# circuit.net
KiCad netlist of a schematic drawn in EAGLE
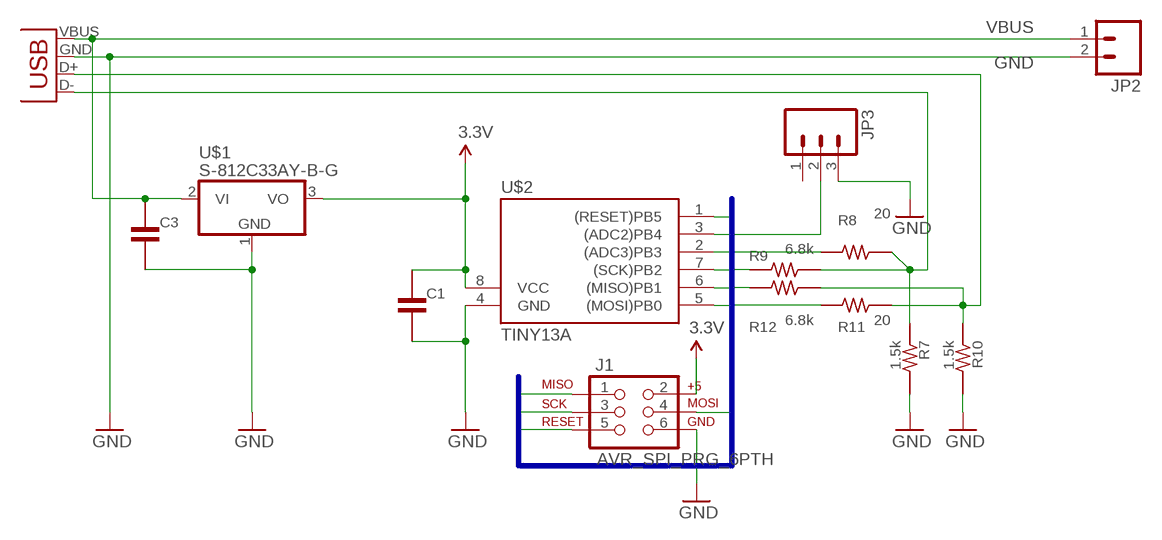
[diagram p0: schematic, sheet 1]

(export (version "E")
  (design (tool "Eeschema 10.0.6"))
  (components
    (comp (ref "C1")
      (value "C-50V-0302-2.54")
      (footprint "eagle-import:50-0302-2.54")
      (libsource (lib "eagle-import") (part "C-50V-0302-2.54"))
    )
    (comp (ref "C3")
      (value "C-50V-0302-2.54")
      (footprint "eagle-import:50-0302-2.54")
      (libsource (lib "eagle-import") (part "C-50V-0302-2.54"))
    )
    (comp (ref "J1")
      (value "AVR_SPI_PRG_6PTH")
      (footprint "eagle-import:2X3")
      (libsource (lib "eagle-import") (part "AVR_SPI_PRG_6PTH"))
    )
    (comp (ref "JP1")
      (value "USB-A-H")
      (footprint "eagle-import:USB-A-H")
      (libsource (lib "eagle-import") (part "USB-A-H"))
    )
    (comp (ref "JP2")
      (value "M02PTH")
      (footprint "eagle-import:1X02")
      (libsource (lib "eagle-import") (part "M02PTH"))
    )
    (comp (ref "JP3")
      (value "M03PTH")
      (footprint "eagle-import:1X03")
      (libsource (lib "eagle-import") (part "M03PTH"))
    )
    (comp (ref "R7")
      (value "1.5k")
      (footprint "eagle-import:1_4W-5.08V")
      (libsource (lib "eagle-import") (part "R-1/4W-05.08-V"))
    )
    (comp (ref "R8")
      (value "20")
      (footprint "eagle-import:1_4W-5.08V")
      (libsource (lib "eagle-import") (part "R-1/4W-05.08-V"))
    )
    (comp (ref "R9")
      (value "6.8k")
      (footprint "eagle-import:1_4W-5.08V")
      (libsource (lib "eagle-import") (part "R-1/4W-05.08-V"))
    )
    (comp (ref "R10")
      (value "1.5k")
      (footprint "eagle-import:1_4W-5.08V")
      (libsource (lib "eagle-import") (part "R-1/4W-05.08-V"))
    )
    (comp (ref "R11")
      (value "20")
      (footprint "eagle-import:1_4W-5.08V")
      (libsource (lib "eagle-import") (part "R-1/4W-05.08-V"))
    )
    (comp (ref "R12")
      (value "6.8k")
      (footprint "eagle-import:1_4W-5.08V")
      (libsource (lib "eagle-import") (part "R-1/4W-05.08-V"))
    )
    (comp (ref "U$1")
      (value "S-812C33AY-B-G")
      (footprint "eagle-import:TO-92")
      (libsource (lib "eagle-import") (part "S-812C"))
    )
    (comp (ref "U$2")
      (value "TINY13A")
      (footprint "eagle-import:DIL08")
      (libsource (lib "eagle-import") (part "TINY138P3"))
    )
  )
  (nets
    (net (code "1") (name "/MISO") (class "Default")
      (node (ref "J1") (pin "1") (pinfunction "1_1") (pintype "passive"))
      (node (ref "R12") (pin "PAD1") (pinfunction "1_PAD1") (pintype "passive"))
      (node (ref "U$2") (pin "6") (pinfunction "(MISO)PB1_6") (pintype "bidirectional"))
    )
    (net (code "2") (name "/MOSI") (class "Default")
      (node (ref "J1") (pin "4") (pinfunction "4_4") (pintype "passive"))
      (node (ref "R11") (pin "PAD1") (pinfunction "1_PAD1") (pintype "passive"))
      (node (ref "U$2") (pin "5") (pinfunction "(MOSI)PB0_5") (pintype "bidirectional"))
    )
    (net (code "3") (name "/RESET") (class "Default")
      (node (ref "J1") (pin "5") (pinfunction "5_5") (pintype "passive"))
      (node (ref "U$2") (pin "1") (pinfunction "(RESET)PB5_1") (pintype "bidirectional"))
    )
    (net (code "4") (name "/SCK") (class "Default")
      (node (ref "J1") (pin "3") (pinfunction "3_3") (pintype "passive"))
      (node (ref "R9") (pin "PAD1") (pinfunction "1_PAD1") (pintype "passive"))
      (node (ref "U$2") (pin "7") (pinfunction "(SCK)PB2_7") (pintype "bidirectional"))
    )
    (net (code "5") (name "/VBUS") (class "Default")
      (node (ref "C3") (pin "PAD1") (pinfunction "1_PAD1") (pintype "passive"))
      (node (ref "JP1") (pin "VBUS") (pinfunction "GND_VBUS") (pintype "bidirectional"))
      (node (ref "JP2") (pin "1") (pinfunction "1_1") (pintype "passive"))
      (node (ref "U$1") (pin "2") (pinfunction "VI_2") (pintype "input"))
    )
    (net (code "6") (name "3.3V") (class "Default")
      (node (ref "C1") (pin "PAD1") (pinfunction "1_PAD1") (pintype "passive"))
      (node (ref "J1") (pin "2") (pinfunction "2_2") (pintype "passive"))
      (node (ref "U$1") (pin "3") (pinfunction "VO_3") (pintype "passive"))
      (node (ref "U$2") (pin "8") (pinfunction "VCC_8") (pintype "power_in"))
    )
    (net (code "7") (name "GND") (class "Default")
      (node (ref "C1") (pin "PAD2") (pinfunction "2_PAD2") (pintype "passive"))
      (node (ref "C3") (pin "PAD2") (pinfunction "2_PAD2") (pintype "passive"))
      (node (ref "J1") (pin "6") (pinfunction "6_6") (pintype "passive"))
      (node (ref "JP1") (pin "GND") (pinfunction "VBUS_GND") (pintype "bidirectional"))
      (node (ref "JP2") (pin "2") (pinfunction "2_2") (pintype "passive"))
      (node (ref "JP3") (pin "3") (pinfunction "3_3") (pintype "passive"))
      (node (ref "R10") (pin "PAD2") (pinfunction "2_PAD2") (pintype "passive"))
      (node (ref "R7") (pin "PAD2") (pinfunction "2_PAD2") (pintype "passive"))
      (node (ref "U$1") (pin "1") (pinfunction "GND_1") (pintype "passive"))
      (node (ref "U$2") (pin "4") (pinfunction "GND_4") (pintype "power_in"))
    )
    (net (code "8") (name "Net-(JP1-D+)") (class "Default")
      (node (ref "JP1") (pin "D-") (pinfunction "D+_D-") (pintype "bidirectional"))
      (node (ref "R7") (pin "PAD1") (pinfunction "1_PAD1") (pintype "passive"))
      (node (ref "R8") (pin "PAD2") (pinfunction "2_PAD2") (pintype "passive"))
      (node (ref "R9") (pin "PAD2") (pinfunction "2_PAD2") (pintype "passive"))
    )
    (net (code "9") (name "Net-(JP1-D-)") (class "Default")
      (node (ref "JP1") (pin "D+") (pinfunction "D-_D+") (pintype "bidirectional"))
      (node (ref "R10") (pin "PAD1") (pinfunction "1_PAD1") (pintype "passive"))
      (node (ref "R11") (pin "PAD2") (pinfunction "2_PAD2") (pintype "passive"))
      (node (ref "R12") (pin "PAD2") (pinfunction "2_PAD2") (pintype "passive"))
    )
    (net (code "10") (name "Net-(R8-1)") (class "Default")
      (node (ref "R8") (pin "PAD1") (pinfunction "1_PAD1") (pintype "passive"))
      (node (ref "U$2") (pin "2") (pinfunction "(ADC3)PB3_2") (pintype "bidirectional"))
    )
    (net (code "11") (name "Net-(U$2-(ADC2)PB4)") (class "Default")
      (node (ref "JP3") (pin "2") (pinfunction "2_2") (pintype "passive"))
      (node (ref "U$2") (pin "3") (pinfunction "(ADC2)PB4_3") (pintype "bidirectional"))
    )
    (net (code "12") (name "unconnected-(JP3-Pad1)") (class "Default")
      (node (ref "JP3") (pin "1") (pinfunction "1_1") (pintype "passive"))
    )
  )
)
